# contactor_control.net
KiCad netlist of a schematic drawn in Altium Designer
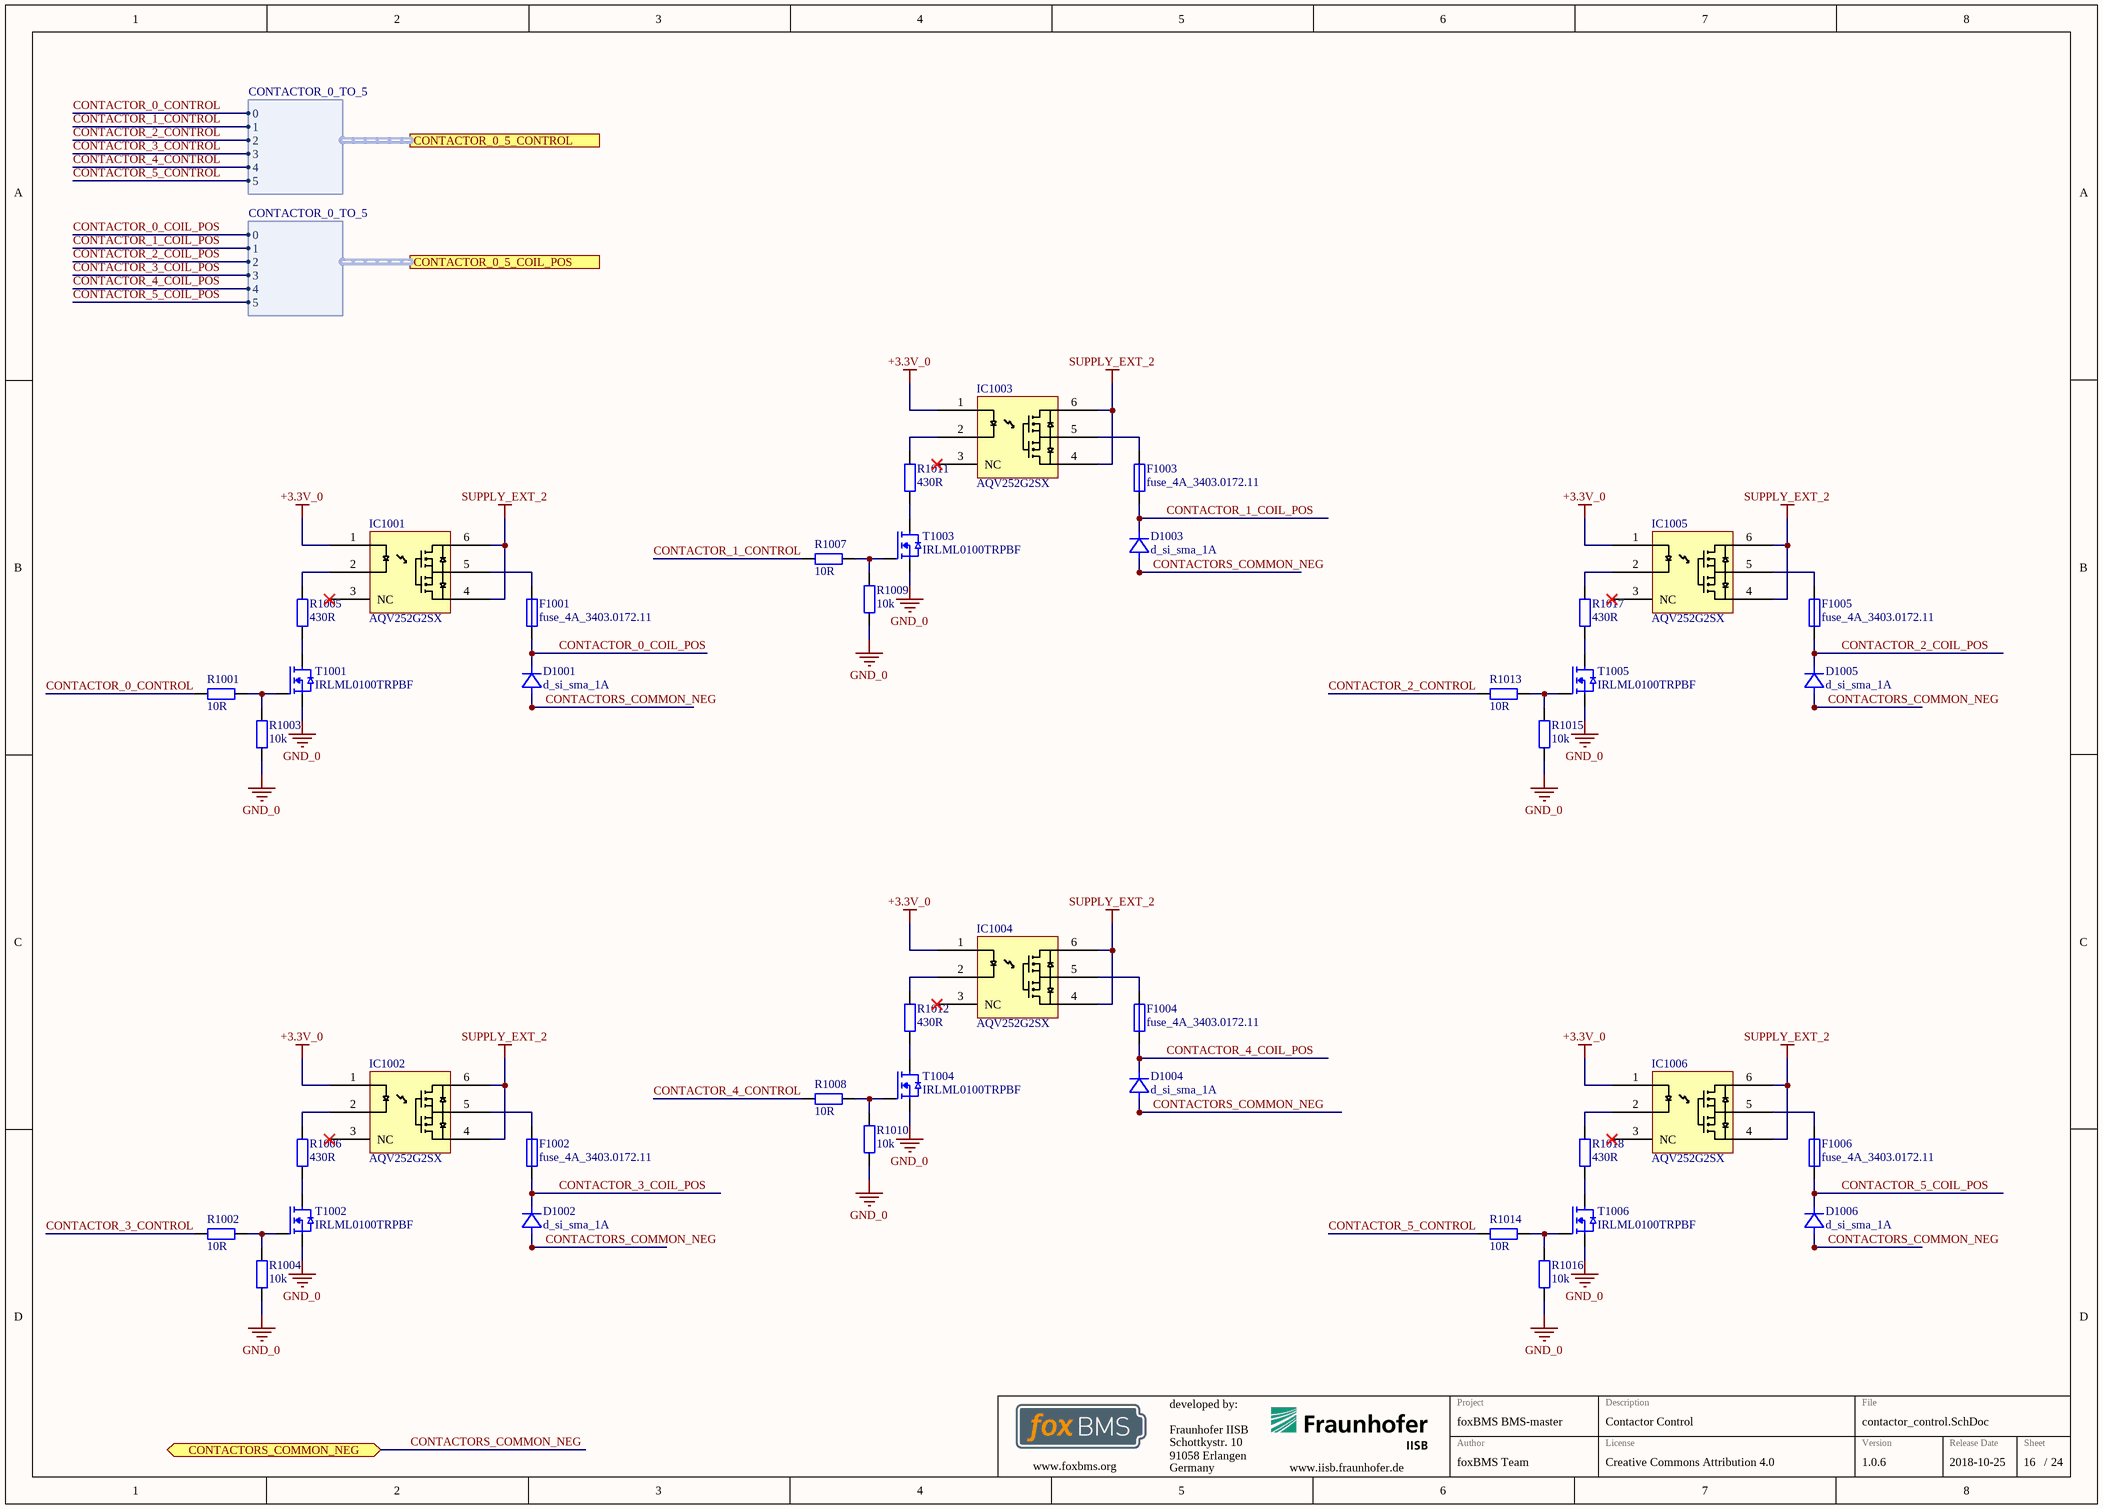
[diagram p0: contactor_control.SchDoc]

(export (version "E")
  (design (tool "Eeschema 10.0.6"))
  (components
    (comp (ref "D1001")
      (value "d_si_sma_1A")
      (footprint "DIOM4326X24N")
      (description "Standard Recovery Diode, 100 V, 1 A, Single, 1 V, 2 µs, 30 A")
      (fields (field (name "MANUFACTURER") "ON Semiconductor"))
      (libsource (lib "OE750") (part "D"))
    )
    (comp (ref "D1002")
      (value "d_si_sma_1A")
      (footprint "DIOM4326X24N")
      (description "Standard Recovery Diode, 100 V, 1 A, Single, 1 V, 2 µs, 30 A")
      (fields (field (name "MANUFACTURER") "ON Semiconductor"))
      (libsource (lib "OE750") (part "D"))
    )
    (comp (ref "D1003")
      (value "d_si_sma_1A")
      (footprint "DIOM4326X24N")
      (description "Standard Recovery Diode, 100 V, 1 A, Single, 1 V, 2 µs, 30 A")
      (fields (field (name "MANUFACTURER") "ON Semiconductor"))
      (libsource (lib "OE750") (part "D"))
    )
    (comp (ref "D1004")
      (value "d_si_sma_1A")
      (footprint "DIOM4326X24N")
      (description "Standard Recovery Diode, 100 V, 1 A, Single, 1 V, 2 µs, 30 A")
      (fields (field (name "MANUFACTURER") "ON Semiconductor"))
      (libsource (lib "OE750") (part "D"))
    )
    (comp (ref "D1005")
      (value "d_si_sma_1A")
      (footprint "DIOM4326X24N")
      (description "Standard Recovery Diode, 100 V, 1 A, Single, 1 V, 2 µs, 30 A")
      (fields (field (name "MANUFACTURER") "ON Semiconductor"))
      (libsource (lib "OE750") (part "D"))
    )
    (comp (ref "D1006")
      (value "d_si_sma_1A")
      (footprint "DIOM4326X24N")
      (description "Standard Recovery Diode, 100 V, 1 A, Single, 1 V, 2 µs, 30 A")
      (fields (field (name "MANUFACTURER") "ON Semiconductor"))
      (libsource (lib "OE750") (part "D"))
    )
    (comp (ref "F1001")
      (value "fuse_4A_3403.0172.11")
      (footprint "Schurter_UMT_250")
      (description "Schurter SMD Fuse 4.0A UMT 3403.0172.11")
      (fields (field (name "MANUFACTURER") "Schurter"))
      (libsource (lib "OE750") (part "R_Fuse"))
    )
    (comp (ref "F1002")
      (value "fuse_4A_3403.0172.11")
      (footprint "Schurter_UMT_250")
      (description "Schurter SMD Fuse 4.0A UMT 3403.0172.11")
      (fields (field (name "MANUFACTURER") "Schurter"))
      (libsource (lib "OE750") (part "R_Fuse"))
    )
    (comp (ref "F1003")
      (value "fuse_4A_3403.0172.11")
      (footprint "Schurter_UMT_250")
      (description "Schurter SMD Fuse 4.0A UMT 3403.0172.11")
      (fields (field (name "MANUFACTURER") "Schurter"))
      (libsource (lib "OE750") (part "R_Fuse"))
    )
    (comp (ref "F1004")
      (value "fuse_4A_3403.0172.11")
      (footprint "Schurter_UMT_250")
      (description "Schurter SMD Fuse 4.0A UMT 3403.0172.11")
      (fields (field (name "MANUFACTURER") "Schurter"))
      (libsource (lib "OE750") (part "R_Fuse"))
    )
    (comp (ref "F1005")
      (value "fuse_4A_3403.0172.11")
      (footprint "Schurter_UMT_250")
      (description "Schurter SMD Fuse 4.0A UMT 3403.0172.11")
      (fields (field (name "MANUFACTURER") "Schurter"))
      (libsource (lib "OE750") (part "R_Fuse"))
    )
    (comp (ref "F1006")
      (value "fuse_4A_3403.0172.11")
      (footprint "Schurter_UMT_250")
      (description "Schurter SMD Fuse 4.0A UMT 3403.0172.11")
      (fields (field (name "MANUFACTURER") "Schurter"))
      (libsource (lib "OE750") (part "R_Fuse"))
    )
    (comp (ref "IC1001")
      (value "AQV252G2SX")
      (footprint "SOP254P680X220-6N")
      (description "PhotoMOS Relay")
      (fields (field (name "MANUFACTURER") "Panasonic"))
      (libsource (lib "OE750") (part "AQV252G2SX"))
    )
    (comp (ref "IC1002")
      (value "AQV252G2SX")
      (footprint "SOP254P680X220-6N")
      (description "PhotoMOS Relay")
      (fields (field (name "MANUFACTURER") "Panasonic"))
      (libsource (lib "OE750") (part "AQV252G2SX"))
    )
    (comp (ref "IC1003")
      (value "AQV252G2SX")
      (footprint "SOP254P680X220-6N")
      (description "PhotoMOS Relay")
      (fields (field (name "MANUFACTURER") "Panasonic"))
      (libsource (lib "OE750") (part "AQV252G2SX"))
    )
    (comp (ref "IC1004")
      (value "AQV252G2SX")
      (footprint "SOP254P680X220-6N")
      (description "PhotoMOS Relay")
      (fields (field (name "MANUFACTURER") "Panasonic"))
      (libsource (lib "OE750") (part "AQV252G2SX"))
    )
    (comp (ref "IC1005")
      (value "AQV252G2SX")
      (footprint "SOP254P680X220-6N")
      (description "PhotoMOS Relay")
      (fields (field (name "MANUFACTURER") "Panasonic"))
      (libsource (lib "OE750") (part "AQV252G2SX"))
    )
    (comp (ref "IC1006")
      (value "AQV252G2SX")
      (footprint "SOP254P680X220-6N")
      (description "PhotoMOS Relay")
      (fields (field (name "MANUFACTURER") "Panasonic"))
      (libsource (lib "OE750") (part "AQV252G2SX"))
    )
    (comp (ref "R1001")
      (value "10R")
      (footprint "RESC1608X05N")
      (description "SMD Resistor 10R 0603")
      (fields (field (name "PART NUMBER") "gen_R_10R_0603") (field (name "TOLERANCE") "1%"))
      (libsource (lib "OE750") (part "R"))
    )
    (comp (ref "R1002")
      (value "10R")
      (footprint "RESC1608X05N")
      (description "SMD Resistor 10R 0603")
      (fields (field (name "PART NUMBER") "gen_R_10R_0603") (field (name "TOLERANCE") "1%"))
      (libsource (lib "OE750") (part "R"))
    )
    (comp (ref "R1003")
      (value "10k")
      (footprint "RESC1608X05N")
      (description "SMD Resistor 10k 0603")
      (fields (field (name "PART NUMBER") "gen_R_10k_0603") (field (name "TOLERANCE") "1%"))
      (libsource (lib "OE750") (part "R"))
    )
    (comp (ref "R1004")
      (value "10k")
      (footprint "RESC1608X05N")
      (description "SMD Resistor 10k 0603")
      (fields (field (name "PART NUMBER") "gen_R_10k_0603") (field (name "TOLERANCE") "1%"))
      (libsource (lib "OE750") (part "R"))
    )
    (comp (ref "R1005")
      (value "430R")
      (footprint "RESC1608X05N")
      (description "SMD Resistor 430R 0603")
      (fields (field (name "PART NUMBER") "gen_R_430R_0603") (field (name "TOLERANCE") "1%"))
      (libsource (lib "OE750") (part "R"))
    )
    (comp (ref "R1006")
      (value "430R")
      (footprint "RESC1608X05N")
      (description "SMD Resistor 430R 0603")
      (fields (field (name "PART NUMBER") "gen_R_430R_0603") (field (name "TOLERANCE") "1%"))
      (libsource (lib "OE750") (part "R"))
    )
    (comp (ref "R1007")
      (value "10R")
      (footprint "RESC1608X05N")
      (description "SMD Resistor 10R 0603")
      (fields (field (name "PART NUMBER") "gen_R_10R_0603") (field (name "TOLERANCE") "1%"))
      (libsource (lib "OE750") (part "R"))
    )
    (comp (ref "R1008")
      (value "10R")
      (footprint "RESC1608X05N")
      (description "SMD Resistor 10R 0603")
      (fields (field (name "PART NUMBER") "gen_R_10R_0603") (field (name "TOLERANCE") "1%"))
      (libsource (lib "OE750") (part "R"))
    )
    (comp (ref "R1009")
      (value "10k")
      (footprint "RESC1608X05N")
      (description "SMD Resistor 10k 0603")
      (fields (field (name "PART NUMBER") "gen_R_10k_0603") (field (name "TOLERANCE") "1%"))
      (libsource (lib "OE750") (part "R"))
    )
    (comp (ref "R1010")
      (value "10k")
      (footprint "RESC1608X05N")
      (description "SMD Resistor 10k 0603")
      (fields (field (name "PART NUMBER") "gen_R_10k_0603") (field (name "TOLERANCE") "1%"))
      (libsource (lib "OE750") (part "R"))
    )
    (comp (ref "R1011")
      (value "430R")
      (footprint "RESC1608X05N")
      (description "SMD Resistor 430R 0603")
      (fields (field (name "PART NUMBER") "gen_R_430R_0603") (field (name "TOLERANCE") "1%"))
      (libsource (lib "OE750") (part "R"))
    )
    (comp (ref "R1012")
      (value "430R")
      (footprint "RESC1608X05N")
      (description "SMD Resistor 430R 0603")
      (fields (field (name "PART NUMBER") "gen_R_430R_0603") (field (name "TOLERANCE") "1%"))
      (libsource (lib "OE750") (part "R"))
    )
    (comp (ref "R1013")
      (value "10R")
      (footprint "RESC1608X05N")
      (description "SMD Resistor 10R 0603")
      (fields (field (name "PART NUMBER") "gen_R_10R_0603") (field (name "TOLERANCE") "1%"))
      (libsource (lib "OE750") (part "R"))
    )
    (comp (ref "R1014")
      (value "10R")
      (footprint "RESC1608X05N")
      (description "SMD Resistor 10R 0603")
      (fields (field (name "PART NUMBER") "gen_R_10R_0603") (field (name "TOLERANCE") "1%"))
      (libsource (lib "OE750") (part "R"))
    )
    (comp (ref "R1015")
      (value "10k")
      (footprint "RESC1608X05N")
      (description "SMD Resistor 10k 0603")
      (fields (field (name "PART NUMBER") "gen_R_10k_0603") (field (name "TOLERANCE") "1%"))
      (libsource (lib "OE750") (part "R"))
    )
    (comp (ref "R1016")
      (value "10k")
      (footprint "RESC1608X05N")
      (description "SMD Resistor 10k 0603")
      (fields (field (name "PART NUMBER") "gen_R_10k_0603") (field (name "TOLERANCE") "1%"))
      (libsource (lib "OE750") (part "R"))
    )
    (comp (ref "R1017")
      (value "430R")
      (footprint "RESC1608X05N")
      (description "SMD Resistor 430R 0603")
      (fields (field (name "PART NUMBER") "gen_R_430R_0603") (field (name "TOLERANCE") "1%"))
      (libsource (lib "OE750") (part "R"))
    )
    (comp (ref "R1018")
      (value "430R")
      (footprint "RESC1608X05N")
      (description "SMD Resistor 430R 0603")
      (fields (field (name "PART NUMBER") "gen_R_430R_0603") (field (name "TOLERANCE") "1%"))
      (libsource (lib "OE750") (part "R"))
    )
    (comp (ref "T1001")
      (value "IRLML0100TRPBF")
      (footprint "SOT95P237X110-3N")
      (description "MOSFET-Transistor, n-Kanal, 1.6 A, 100 V, 0.178 ohm, 10 V, 2.5 V")
      (fields (field (name "MANUFACTURER") "Infineon"))
      (libsource (lib "OE750") (part "NMOS"))
    )
    (comp (ref "T1002")
      (value "IRLML0100TRPBF")
      (footprint "SOT95P237X110-3N")
      (description "MOSFET-Transistor, n-Kanal, 1.6 A, 100 V, 0.178 ohm, 10 V, 2.5 V")
      (fields (field (name "MANUFACTURER") "Infineon"))
      (libsource (lib "OE750") (part "NMOS"))
    )
    (comp (ref "T1003")
      (value "IRLML0100TRPBF")
      (footprint "SOT95P237X110-3N")
      (description "MOSFET-Transistor, n-Kanal, 1.6 A, 100 V, 0.178 ohm, 10 V, 2.5 V")
      (fields (field (name "MANUFACTURER") "Infineon"))
      (libsource (lib "OE750") (part "NMOS"))
    )
    (comp (ref "T1004")
      (value "IRLML0100TRPBF")
      (footprint "SOT95P237X110-3N")
      (description "MOSFET-Transistor, n-Kanal, 1.6 A, 100 V, 0.178 ohm, 10 V, 2.5 V")
      (fields (field (name "MANUFACTURER") "Infineon"))
      (libsource (lib "OE750") (part "NMOS"))
    )
    (comp (ref "T1005")
      (value "IRLML0100TRPBF")
      (footprint "SOT95P237X110-3N")
      (description "MOSFET-Transistor, n-Kanal, 1.6 A, 100 V, 0.178 ohm, 10 V, 2.5 V")
      (fields (field (name "MANUFACTURER") "Infineon"))
      (libsource (lib "OE750") (part "NMOS"))
    )
    (comp (ref "T1006")
      (value "IRLML0100TRPBF")
      (footprint "SOT95P237X110-3N")
      (description "MOSFET-Transistor, n-Kanal, 1.6 A, 100 V, 0.178 ohm, 10 V, 2.5 V")
      (fields (field (name "MANUFACTURER") "Infineon"))
      (libsource (lib "OE750") (part "NMOS"))
    )
  )
  (nets
    (net (code "2") (name "+3.3V_0") (class "Default")
      (node (ref "IC1001") (pin "1") (pintype "passive"))
      (node (ref "IC1002") (pin "1") (pintype "passive"))
      (node (ref "IC1003") (pin "1") (pintype "passive"))
      (node (ref "IC1004") (pin "1") (pintype "passive"))
      (node (ref "IC1005") (pin "1") (pintype "passive"))
      (node (ref "IC1006") (pin "1") (pintype "passive"))
    )
    (net (code "3") (name "/CONTACTORS_COMMON_NEG") (class "Default")
      (node (ref "D1001") (pin "2") (pinfunction "A_2") (pintype "passive"))
      (node (ref "D1002") (pin "2") (pinfunction "A_2") (pintype "passive"))
      (node (ref "D1003") (pin "2") (pinfunction "A_2") (pintype "passive"))
      (node (ref "D1004") (pin "2") (pinfunction "A_2") (pintype "passive"))
      (node (ref "D1005") (pin "2") (pinfunction "A_2") (pintype "passive"))
      (node (ref "D1006") (pin "2") (pinfunction "A_2") (pintype "passive"))
    )
    (net (code "4") (name "/CONTACTOR_0_COIL_POS") (class "Default")
      (node (ref "D1001") (pin "1") (pinfunction "K_1") (pintype "passive"))
      (node (ref "F1001") (pin "2") (pinfunction "2_2") (pintype "passive"))
    )
    (net (code "5") (name "/CONTACTOR_0_CONTROL") (class "Default")
      (node (ref "R1001") (pin "2") (pinfunction "2_2") (pintype "passive"))
    )
    (net (code "6") (name "/CONTACTOR_1_COIL_POS") (class "Default")
      (node (ref "D1003") (pin "1") (pinfunction "K_1") (pintype "passive"))
      (node (ref "F1003") (pin "2") (pinfunction "2_2") (pintype "passive"))
    )
    (net (code "7") (name "/CONTACTOR_1_CONTROL") (class "Default")
      (node (ref "R1007") (pin "2") (pinfunction "2_2") (pintype "passive"))
    )
    (net (code "8") (name "/CONTACTOR_2_COIL_POS") (class "Default")
      (node (ref "D1005") (pin "1") (pinfunction "K_1") (pintype "passive"))
      (node (ref "F1005") (pin "2") (pinfunction "2_2") (pintype "passive"))
    )
    (net (code "9") (name "/CONTACTOR_2_CONTROL") (class "Default")
      (node (ref "R1013") (pin "2") (pinfunction "2_2") (pintype "passive"))
    )
    (net (code "10") (name "/CONTACTOR_3_COIL_POS") (class "Default")
      (node (ref "D1002") (pin "1") (pinfunction "K_1") (pintype "passive"))
      (node (ref "F1002") (pin "2") (pinfunction "2_2") (pintype "passive"))
    )
    (net (code "11") (name "/CONTACTOR_3_CONTROL") (class "Default")
      (node (ref "R1002") (pin "2") (pinfunction "2_2") (pintype "passive"))
    )
    (net (code "12") (name "/CONTACTOR_4_COIL_POS") (class "Default")
      (node (ref "D1004") (pin "1") (pinfunction "K_1") (pintype "passive"))
      (node (ref "F1004") (pin "2") (pinfunction "2_2") (pintype "passive"))
    )
    (net (code "13") (name "/CONTACTOR_4_CONTROL") (class "Default")
      (node (ref "R1008") (pin "2") (pinfunction "2_2") (pintype "passive"))
    )
    (net (code "14") (name "/CONTACTOR_5_COIL_POS") (class "Default")
      (node (ref "D1006") (pin "1") (pinfunction "K_1") (pintype "passive"))
      (node (ref "F1006") (pin "2") (pinfunction "2_2") (pintype "passive"))
    )
    (net (code "15") (name "/CONTACTOR_5_CONTROL") (class "Default")
      (node (ref "R1014") (pin "2") (pinfunction "2_2") (pintype "passive"))
    )
    (net (code "17") (name "GND_0") (class "Default")
      (node (ref "R1003") (pin "1") (pinfunction "1_1") (pintype "passive"))
      (node (ref "R1004") (pin "1") (pinfunction "1_1") (pintype "passive"))
      (node (ref "R1009") (pin "1") (pinfunction "1_1") (pintype "passive"))
      (node (ref "R1010") (pin "1") (pinfunction "1_1") (pintype "passive"))
      (node (ref "R1015") (pin "1") (pinfunction "1_1") (pintype "passive"))
      (node (ref "R1016") (pin "1") (pinfunction "1_1") (pintype "passive"))
      (node (ref "T1001") (pin "S") (pinfunction "S_S") (pintype "passive"))
      (node (ref "T1002") (pin "S") (pinfunction "S_S") (pintype "passive"))
      (node (ref "T1003") (pin "S") (pinfunction "S_S") (pintype "passive"))
      (node (ref "T1004") (pin "S") (pinfunction "S_S") (pintype "passive"))
      (node (ref "T1005") (pin "S") (pinfunction "S_S") (pintype "passive"))
      (node (ref "T1006") (pin "S") (pinfunction "S_S") (pintype "passive"))
    )
    (net (code "18") (name "Net-(F1001-Pad1)") (class "Default")
      (node (ref "F1001") (pin "1") (pinfunction "1_1") (pintype "passive"))
      (node (ref "IC1001") (pin "5") (pintype "passive"))
    )
    (net (code "19") (name "Net-(F1002-Pad1)") (class "Default")
      (node (ref "F1002") (pin "1") (pinfunction "1_1") (pintype "passive"))
      (node (ref "IC1002") (pin "5") (pintype "passive"))
    )
    (net (code "20") (name "Net-(F1003-Pad1)") (class "Default")
      (node (ref "F1003") (pin "1") (pinfunction "1_1") (pintype "passive"))
      (node (ref "IC1003") (pin "5") (pintype "passive"))
    )
    (net (code "21") (name "Net-(F1004-Pad1)") (class "Default")
      (node (ref "F1004") (pin "1") (pinfunction "1_1") (pintype "passive"))
      (node (ref "IC1004") (pin "5") (pintype "passive"))
    )
    (net (code "22") (name "Net-(F1005-Pad1)") (class "Default")
      (node (ref "F1005") (pin "1") (pinfunction "1_1") (pintype "passive"))
      (node (ref "IC1005") (pin "5") (pintype "passive"))
    )
    (net (code "23") (name "Net-(F1006-Pad1)") (class "Default")
      (node (ref "F1006") (pin "1") (pinfunction "1_1") (pintype "passive"))
      (node (ref "IC1006") (pin "5") (pintype "passive"))
    )
    (net (code "24") (name "Net-(IC1001-Pad2)") (class "Default")
      (node (ref "IC1001") (pin "2") (pintype "power_in"))
      (node (ref "R1005") (pin "2") (pinfunction "2_2") (pintype "passive"))
    )
    (net (code "25") (name "Net-(IC1002-Pad2)") (class "Default")
      (node (ref "IC1002") (pin "2") (pintype "power_in"))
      (node (ref "R1006") (pin "2") (pinfunction "2_2") (pintype "passive"))
    )
    (net (code "26") (name "Net-(IC1003-Pad2)") (class "Default")
      (node (ref "IC1003") (pin "2") (pintype "power_in"))
      (node (ref "R1011") (pin "2") (pinfunction "2_2") (pintype "passive"))
    )
    (net (code "27") (name "Net-(IC1004-Pad2)") (class "Default")
      (node (ref "IC1004") (pin "2") (pintype "power_in"))
      (node (ref "R1012") (pin "2") (pinfunction "2_2") (pintype "passive"))
    )
    (net (code "28") (name "Net-(IC1005-Pad2)") (class "Default")
      (node (ref "IC1005") (pin "2") (pintype "power_in"))
      (node (ref "R1017") (pin "2") (pinfunction "2_2") (pintype "passive"))
    )
    (net (code "29") (name "Net-(IC1006-Pad2)") (class "Default")
      (node (ref "IC1006") (pin "2") (pintype "power_in"))
      (node (ref "R1018") (pin "2") (pinfunction "2_2") (pintype "passive"))
    )
    (net (code "30") (name "Net-(R1001-Pad1)") (class "Default")
      (node (ref "R1001") (pin "1") (pinfunction "1_1") (pintype "passive"))
      (node (ref "R1003") (pin "2") (pinfunction "2_2") (pintype "passive"))
      (node (ref "T1001") (pin "G") (pinfunction "G_G") (pintype "passive"))
    )
    (net (code "31") (name "Net-(R1002-Pad1)") (class "Default")
      (node (ref "R1002") (pin "1") (pinfunction "1_1") (pintype "passive"))
      (node (ref "R1004") (pin "2") (pinfunction "2_2") (pintype "passive"))
      (node (ref "T1002") (pin "G") (pinfunction "G_G") (pintype "passive"))
    )
    (net (code "32") (name "Net-(R1005-Pad1)") (class "Default")
      (node (ref "R1005") (pin "1") (pinfunction "1_1") (pintype "passive"))
      (node (ref "T1001") (pin "D") (pinfunction "D_D") (pintype "passive"))
    )
    (net (code "33") (name "Net-(R1006-Pad1)") (class "Default")
      (node (ref "R1006") (pin "1") (pinfunction "1_1") (pintype "passive"))
      (node (ref "T1002") (pin "D") (pinfunction "D_D") (pintype "passive"))
    )
    (net (code "34") (name "Net-(R1007-Pad1)") (class "Default")
      (node (ref "R1007") (pin "1") (pinfunction "1_1") (pintype "passive"))
      (node (ref "R1009") (pin "2") (pinfunction "2_2") (pintype "passive"))
      (node (ref "T1003") (pin "G") (pinfunction "G_G") (pintype "passive"))
    )
    (net (code "35") (name "Net-(R1008-Pad1)") (class "Default")
      (node (ref "R1008") (pin "1") (pinfunction "1_1") (pintype "passive"))
      (node (ref "R1010") (pin "2") (pinfunction "2_2") (pintype "passive"))
      (node (ref "T1004") (pin "G") (pinfunction "G_G") (pintype "passive"))
    )
    (net (code "36") (name "Net-(R1011-Pad1)") (class "Default")
      (node (ref "R1011") (pin "1") (pinfunction "1_1") (pintype "passive"))
      (node (ref "T1003") (pin "D") (pinfunction "D_D") (pintype "passive"))
    )
    (net (code "37") (name "Net-(R1012-Pad1)") (class "Default")
      (node (ref "R1012") (pin "1") (pinfunction "1_1") (pintype "passive"))
      (node (ref "T1004") (pin "D") (pinfunction "D_D") (pintype "passive"))
    )
    (net (code "38") (name "Net-(R1013-Pad1)") (class "Default")
      (node (ref "R1013") (pin "1") (pinfunction "1_1") (pintype "passive"))
      (node (ref "R1015") (pin "2") (pinfunction "2_2") (pintype "passive"))
      (node (ref "T1005") (pin "G") (pinfunction "G_G") (pintype "passive"))
    )
    (net (code "39") (name "Net-(R1014-Pad1)") (class "Default")
      (node (ref "R1014") (pin "1") (pinfunction "1_1") (pintype "passive"))
      (node (ref "R1016") (pin "2") (pinfunction "2_2") (pintype "passive"))
      (node (ref "T1006") (pin "G") (pinfunction "G_G") (pintype "passive"))
    )
    (net (code "40") (name "Net-(R1017-Pad1)") (class "Default")
      (node (ref "R1017") (pin "1") (pinfunction "1_1") (pintype "passive"))
      (node (ref "T1005") (pin "D") (pinfunction "D_D") (pintype "passive"))
    )
    (net (code "41") (name "Net-(R1018-Pad1)") (class "Default")
      (node (ref "R1018") (pin "1") (pinfunction "1_1") (pintype "passive"))
      (node (ref "T1006") (pin "D") (pinfunction "D_D") (pintype "passive"))
    )
    (net (code "42") (name "SUPPLY_EXT_2") (class "Default")
      (node (ref "IC1001") (pin "4") (pintype "passive"))
      (node (ref "IC1001") (pin "6") (pintype "passive"))
      (node (ref "IC1002") (pin "4") (pintype "passive"))
      (node (ref "IC1002") (pin "6") (pintype "passive"))
      (node (ref "IC1003") (pin "4") (pintype "passive"))
      (node (ref "IC1003") (pin "6") (pintype "passive"))
      (node (ref "IC1004") (pin "4") (pintype "passive"))
      (node (ref "IC1004") (pin "6") (pintype "passive"))
      (node (ref "IC1005") (pin "4") (pintype "passive"))
      (node (ref "IC1005") (pin "6") (pintype "passive"))
      (node (ref "IC1006") (pin "4") (pintype "passive"))
      (node (ref "IC1006") (pin "6") (pintype "passive"))
    )
    (net (code "43") (name "unconnected-(IC1001-NC-Pad3)") (class "Default")
      (node (ref "IC1001") (pin "3") (pinfunction "NC_3") (pintype "passive+no_connect"))
    )
    (net (code "44") (name "unconnected-(IC1002-NC-Pad3)") (class "Default")
      (node (ref "IC1002") (pin "3") (pinfunction "NC_3") (pintype "passive+no_connect"))
    )
    (net (code "45") (name "unconnected-(IC1003-NC-Pad3)") (class "Default")
      (node (ref "IC1003") (pin "3") (pinfunction "NC_3") (pintype "passive+no_connect"))
    )
    (net (code "46") (name "unconnected-(IC1004-NC-Pad3)") (class "Default")
      (node (ref "IC1004") (pin "3") (pinfunction "NC_3") (pintype "passive+no_connect"))
    )
    (net (code "47") (name "unconnected-(IC1005-NC-Pad3)") (class "Default")
      (node (ref "IC1005") (pin "3") (pinfunction "NC_3") (pintype "passive+no_connect"))
    )
    (net (code "48") (name "unconnected-(IC1006-NC-Pad3)") (class "Default")
      (node (ref "IC1006") (pin "3") (pinfunction "NC_3") (pintype "passive+no_connect"))
    )
  )
)
